# UART_USB.net
KiCad netlist of a schematic drawn in Altium Designer
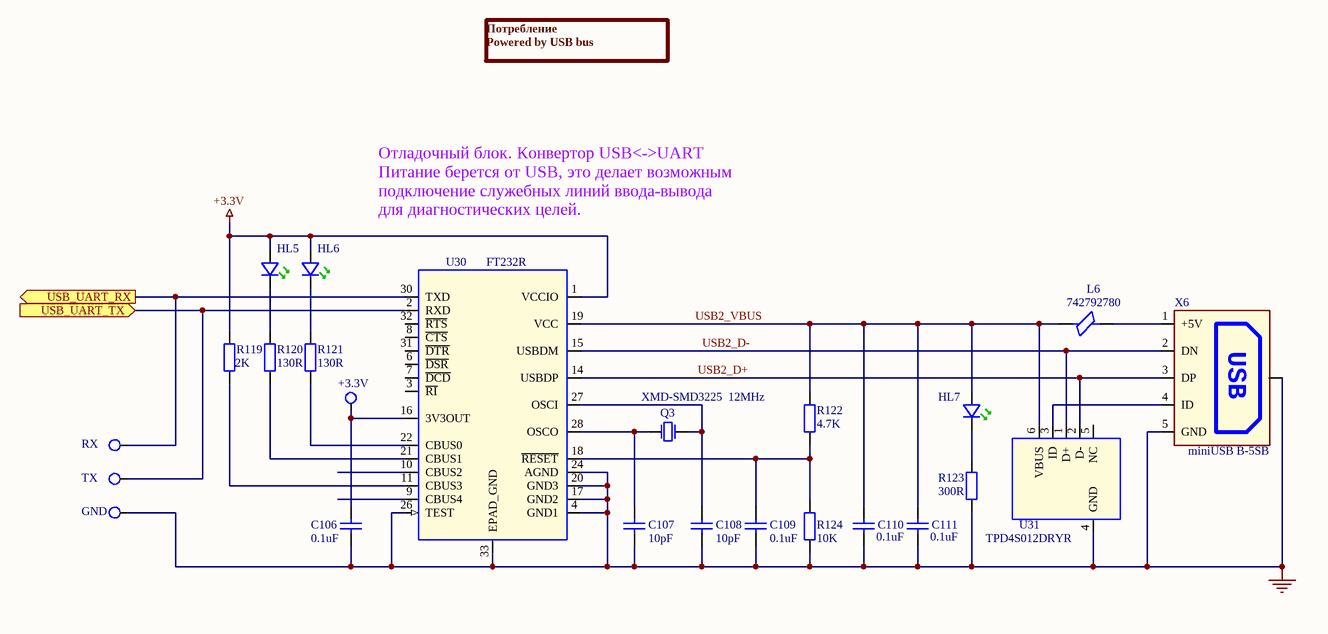
[diagram p0: UART_USB.SchDoc]

(export (version "E")
  (design (tool "Eeschema 10.0.6"))
  (components
    (comp (ref "C106")
      (value "0.1uF")
      (footprint "C0402")
      (description "Конденсатор керамический")
      (fields (field (name "VOLTAGE") "25V") (field (name "Comment") "Cap"))
      (libsource (lib "Terra") (part "Cap"))
    )
    (comp (ref "C107")
      (value "10pF")
      (footprint "C0402")
      (description "GRM1535C1H100J")
      (fields (field (name "Comment") "Cap"))
      (libsource (lib "Terra") (part "Cap"))
    )
    (comp (ref "C108")
      (value "10pF")
      (footprint "C0402")
      (description "GRM1535C1H100J")
      (fields (field (name "Comment") "Cap"))
      (libsource (lib "Terra") (part "Cap"))
    )
    (comp (ref "C109")
      (value "0.1uF")
      (footprint "C0402")
      (description "Конденсатор керамический")
      (fields (field (name "VOLTAGE") "25V") (field (name "Comment") "Cap"))
      (libsource (lib "Terra") (part "Cap"))
    )
    (comp (ref "C110")
      (value "0.1uF")
      (footprint "C0402")
      (description "Конденсатор керамический")
      (fields (field (name "VOLTAGE") "25V") (field (name "Comment") "Cap"))
      (libsource (lib "Terra") (part "Cap"))
    )
    (comp (ref "C111")
      (value "0.1uF")
      (footprint "C0402")
      (description "Конденсатор керамический")
      (fields (field (name "VOLTAGE") "25V") (field (name "Comment") "Cap"))
      (libsource (lib "Terra") (part "Cap"))
    )
    (comp (ref "HL5")
      (value "~")
      (footprint "KP-1608_16x08x11_L")
      (description "1.6X0.8mm SMD  LED")
      (libsource (lib "Terra") (part "ledG_KP-1608MGC_KP-1608"))
    )
    (comp (ref "HL6")
      (value "~")
      (footprint "KP-1608_16x08x11_L")
      (description "1.6X0.8mm SMD  LED")
      (libsource (lib "Terra") (part "ledG_KP-1608MGC_KP-1608"))
    )
    (comp (ref "HL7")
      (value "~")
      (footprint "KP-1608_16x08x11_L")
      (description "1.6X0.8mm SMD  LED")
      (libsource (lib "Terra") (part "ledG_KP-1608MGC_KP-1608"))
    )
    (comp (ref "L6")
      (value "742792780")
      (footprint "L0402")
      (description "Wurth Elektronik EMI FILTERS FERRITE BEAD, 220R@100MHz, 0.35R")
      (libsource (lib "Terra") (part "BEAD_FERRITE_SM"))
    )
    (comp (ref "Q3")
      (value "XMD-SMD3225  12MHz")
      (footprint "KX-5T")
      (description "Chengdu Kingbri Frequency Technology Co., Ltd  12MHz")
      (libsource (lib "common") (part "XTAL"))
    )
    (comp (ref "R119")
      (value "2K")
      (footprint "R0402")
      (description "Резистор")
      (fields (field (name "Comment") "Res2"))
      (libsource (lib "Terra") (part "Res2"))
    )
    (comp (ref "R120")
      (value "130R")
      (footprint "R0402")
      (description "Резистор")
      (fields (field (name "Comment") "Res2"))
      (libsource (lib "Terra") (part "Res2"))
    )
    (comp (ref "R121")
      (value "130R")
      (footprint "R0402")
      (description "Резистор")
      (fields (field (name "Comment") "Res2"))
      (libsource (lib "Terra") (part "Res2"))
    )
    (comp (ref "R122")
      (value "4.7K")
      (footprint "R0402")
      (description "Резистор")
      (fields (field (name "Comment") "Res2"))
      (libsource (lib "") (part "Res2_1"))
    )
    (comp (ref "R123")
      (value "300R")
      (footprint "R0402")
      (description "Резистор")
      (fields (field (name "Comment") "Res2"))
      (libsource (lib "") (part "Res2_1"))
    )
    (comp (ref "R124")
      (value "10K")
      (footprint "R0402")
      (description "Резистор")
      (fields (field (name "Comment") "Res2"))
      (libsource (lib "") (part "Res2_1"))
    )
    (comp (ref "TP21")
      (value "~")
      (footprint "TP_0MM5_1MM0")
      (description "Тестовая точка на плате")
      (fields (field (name "MARKPCB") "+3.3V"))
      (libsource (lib "*") (part "Test_Point"))
    )
    (comp (ref "TP22")
      (value "~")
      (footprint "TP_0MM5_1MM0")
      (description "Тестовая точка на плате")
      (fields (field (name "MARKPCB") "RX"))
      (libsource (lib "*") (part "Test_Point"))
    )
    (comp (ref "TP23")
      (value "~")
      (footprint "TP_0MM5_1MM0")
      (description "Тестовая точка на плате")
      (fields (field (name "MARKPCB") "TX"))
      (libsource (lib "*") (part "Test_Point"))
    )
    (comp (ref "TP24")
      (value "~")
      (footprint "TP_0MM5_1MM0")
      (description "Тестовая точка на плате")
      (fields (field (name "MARKPCB") "GND"))
      (libsource (lib "*") (part "Test_Point"))
    )
    (comp (ref "U30")
      (value "FT232R")
      (footprint "QFN32_FT232RQ_FTD-L")
      (description "USB to serial UART interface")
      (libsource (lib "common") (part "FT232R_2"))
    )
    (comp (ref "U31")
      (value "TPD4S012DRYR")
      (footprint "TPD4S012DRYR")
      (description "Защитные диоды USB")
      (libsource (lib "common") (part "TPD4S012DRYR"))
    )
    (comp (ref "X6")
      (value "miniUSB B-5SB")
      (footprint "USBSMALL")
      (description "5-контактная SMD розетка")
      (fields (field (name "Comment") "USB"))
      (libsource (lib "common") (part "USB"))
    )
  )
  (nets
    (net (code "1") (name "+3.3V") (class "Default")
      (node (ref "HL5") (pin "1") (pinfunction "Anode_1") (pintype "passive"))
      (node (ref "HL6") (pin "1") (pinfunction "Anode_1") (pintype "passive"))
      (node (ref "R119") (pin "2") (pinfunction "2_2") (pintype "passive"))
      (node (ref "U30") (pin "1") (pinfunction "VCCIO_1") (pintype "power_in"))
    )
    (net (code "2") (name "/USB2_D+") (class "Default")
      (node (ref "U30") (pin "14") (pinfunction "USBDP_14") (pintype "passive"))
      (node (ref "U31") (pin "2") (pinfunction "D-_2") (pintype "passive"))
      (node (ref "X6") (pin "3") (pinfunction "DP_3") (pintype "passive"))
    )
    (net (code "3") (name "/USB2_D-") (class "Default")
      (node (ref "U30") (pin "15") (pinfunction "USBDM_15") (pintype "passive"))
      (node (ref "U31") (pin "1") (pinfunction "D+_1") (pintype "passive"))
      (node (ref "X6") (pin "2") (pinfunction "DN_2") (pintype "passive"))
    )
    (net (code "4") (name "/USB2_VBUS") (class "Default")
      (node (ref "C110") (pin "1") (pinfunction "1_1") (pintype "passive"))
      (node (ref "C111") (pin "1") (pinfunction "1_1") (pintype "passive"))
      (node (ref "HL7") (pin "1") (pinfunction "Anode_1") (pintype "passive"))
      (node (ref "L6") (pin "1") (pinfunction "1_1") (pintype "passive"))
      (node (ref "R122") (pin "1") (pinfunction "1_1") (pintype "passive"))
      (node (ref "U30") (pin "19") (pinfunction "VCC_19") (pintype "power_in"))
      (node (ref "U31") (pin "6") (pinfunction "VBUS_6") (pintype "passive"))
    )
    (net (code "5") (name "/USB_UART_RX") (class "Default")
      (node (ref "TP22") (pin "1") (pinfunction "e1_1") (pintype "passive"))
      (node (ref "U30") (pin "30") (pinfunction "TXD_30") (pintype "passive"))
    )
    (net (code "6") (name "/USB_UART_TX") (class "Default")
      (node (ref "TP23") (pin "1") (pinfunction "e1_1") (pintype "passive"))
      (node (ref "U30") (pin "2") (pinfunction "RXD_2") (pintype "passive"))
    )
    (net (code "7") (name "GND") (class "Default")
      (node (ref "C106") (pin "2") (pinfunction "2_2") (pintype "passive"))
      (node (ref "C107") (pin "2") (pinfunction "2_2") (pintype "passive"))
      (node (ref "C108") (pin "2") (pinfunction "2_2") (pintype "passive"))
      (node (ref "C109") (pin "2") (pinfunction "2_2") (pintype "passive"))
      (node (ref "C110") (pin "2") (pinfunction "2_2") (pintype "passive"))
      (node (ref "C111") (pin "2") (pinfunction "2_2") (pintype "passive"))
      (node (ref "R123") (pin "2") (pinfunction "2_2") (pintype "passive"))
      (node (ref "R124") (pin "2") (pinfunction "2_2") (pintype "passive"))
      (node (ref "TP24") (pin "1") (pinfunction "e1_1") (pintype "passive"))
      (node (ref "U30") (pin "17") (pinfunction "GND2_17") (pintype "power_in"))
      (node (ref "U30") (pin "20") (pinfunction "GND3_20") (pintype "power_in"))
      (node (ref "U30") (pin "24") (pinfunction "AGND_24") (pintype "power_in"))
      (node (ref "U30") (pin "26") (pinfunction "TEST_26") (pintype "input"))
      (node (ref "U30") (pin "33") (pinfunction "EPAD_GND_33") (pintype "power_in"))
      (node (ref "U30") (pin "4") (pinfunction "GND1_4") (pintype "power_in"))
      (node (ref "U31") (pin "4") (pinfunction "GND_4") (pintype "passive"))
      (node (ref "X6") (pin "0") (pinfunction "PAD_0") (pintype "passive"))
      (node (ref "X6") (pin "5") (pinfunction "GND_5") (pintype "passive"))
    )
    (net (code "8") (name "Net-(HL5-Cathode)") (class "Default")
      (node (ref "HL5") (pin "2") (pinfunction "Cathode_2") (pintype "passive"))
      (node (ref "R120") (pin "2") (pinfunction "2_2") (pintype "passive"))
    )
    (net (code "9") (name "Net-(HL6-Cathode)") (class "Default")
      (node (ref "HL6") (pin "2") (pinfunction "Cathode_2") (pintype "passive"))
      (node (ref "R121") (pin "2") (pinfunction "2_2") (pintype "passive"))
    )
    (net (code "10") (name "Net-(HL7-Cathode)") (class "Default")
      (node (ref "HL7") (pin "2") (pinfunction "Cathode_2") (pintype "passive"))
      (node (ref "R123") (pin "1") (pinfunction "1_1") (pintype "passive"))
    )
    (net (code "11") (name "Net-(Q3-OSC1)") (class "Default")
      (node (ref "C108") (pin "1") (pinfunction "1_1") (pintype "passive"))
      (node (ref "Q3") (pin "1") (pinfunction "OSC1_1") (pintype "passive"))
      (node (ref "U30") (pin "27") (pinfunction "OSCI_27") (pintype "passive"))
    )
    (net (code "12") (name "Net-(Q3-OSC2)") (class "Default")
      (node (ref "C107") (pin "1") (pinfunction "1_1") (pintype "passive"))
      (node (ref "Q3") (pin "3") (pinfunction "OSC2_3") (pintype "passive"))
      (node (ref "U30") (pin "28") (pinfunction "OSCO_28") (pintype "passive"))
    )
    (net (code "13") (name "Net-(TP21-e1)") (class "Default")
      (node (ref "C106") (pin "1") (pinfunction "1_1") (pintype "passive"))
      (node (ref "TP21") (pin "1") (pinfunction "e1_1") (pintype "passive"))
      (node (ref "U30") (pin "16") (pinfunction "3V3OUT_16") (pintype "power_in"))
    )
    (net (code "14") (name "Net-(U30-CBUS0)") (class "Default")
      (node (ref "R121") (pin "1") (pinfunction "1_1") (pintype "passive"))
      (node (ref "U30") (pin "22") (pinfunction "CBUS0_22") (pintype "passive"))
    )
    (net (code "15") (name "Net-(U30-CBUS1)") (class "Default")
      (node (ref "R120") (pin "1") (pinfunction "1_1") (pintype "passive"))
      (node (ref "U30") (pin "21") (pinfunction "CBUS1_21") (pintype "passive"))
    )
    (net (code "16") (name "Net-(U30-CBUS3)") (class "Default")
      (node (ref "R119") (pin "1") (pinfunction "1_1") (pintype "passive"))
      (node (ref "U30") (pin "11") (pinfunction "CBUS3_11") (pintype "passive"))
    )
    (net (code "17") (name "Net-(U30-~{RESET})") (class "Default")
      (node (ref "C109") (pin "1") (pinfunction "1_1") (pintype "passive"))
      (node (ref "R122") (pin "2") (pinfunction "2_2") (pintype "passive"))
      (node (ref "R124") (pin "1") (pinfunction "1_1") (pintype "passive"))
      (node (ref "U30") (pin "18") (pinfunction "~{RESET}_18") (pintype "passive"))
    )
    (net (code "18") (name "Net-(U31-ID)") (class "Default")
      (node (ref "U31") (pin "3") (pinfunction "ID_3") (pintype "passive"))
      (node (ref "X6") (pin "4") (pinfunction "ID_4") (pintype "passive"))
    )
    (net (code "19") (name "Net-(X6-+5V)") (class "Default")
      (node (ref "L6") (pin "2") (pinfunction "2_2") (pintype "passive"))
      (node (ref "X6") (pin "1") (pinfunction "+5V_1") (pintype "passive"))
    )
    (net (code "20") (name "unconnected-(U30-CBUS2-Pad10)") (class "Default")
      (node (ref "U30") (pin "10") (pinfunction "CBUS2_10") (pintype "passive"))
    )
    (net (code "21") (name "unconnected-(U30-CBUS4-Pad9)") (class "Default")
      (node (ref "U30") (pin "9") (pinfunction "CBUS4_9") (pintype "passive"))
    )
    (net (code "22") (name "unconnected-(U30-~{CTS}-Pad8)") (class "Default")
      (node (ref "U30") (pin "8") (pinfunction "~{CTS}_8") (pintype "passive"))
    )
    (net (code "23") (name "unconnected-(U30-~{DCD}-Pad7)") (class "Default")
      (node (ref "U30") (pin "7") (pinfunction "~{DCD}_7") (pintype "passive"))
    )
    (net (code "24") (name "unconnected-(U30-~{DSR}-Pad6)") (class "Default")
      (node (ref "U30") (pin "6") (pinfunction "~{DSR}_6") (pintype "passive"))
    )
    (net (code "25") (name "unconnected-(U30-~{DTR}-Pad31)") (class "Default")
      (node (ref "U30") (pin "31") (pinfunction "~{DTR}_31") (pintype "passive"))
    )
    (net (code "26") (name "unconnected-(U30-~{RI}-Pad3)") (class "Default")
      (node (ref "U30") (pin "3") (pinfunction "~{RI}_3") (pintype "passive"))
    )
    (net (code "27") (name "unconnected-(U30-~{RTS}-Pad32)") (class "Default")
      (node (ref "U30") (pin "32") (pinfunction "~{RTS}_32") (pintype "passive"))
    )
    (net (code "28") (name "unconnected-(U31-NC-Pad5)") (class "Default")
      (node (ref "U31") (pin "5") (pinfunction "NC_5") (pintype "passive"))
    )
  )
)
